# G474VET6_V3_1.net
KiCad netlist of a schematic drawn in EasyEDA Pro
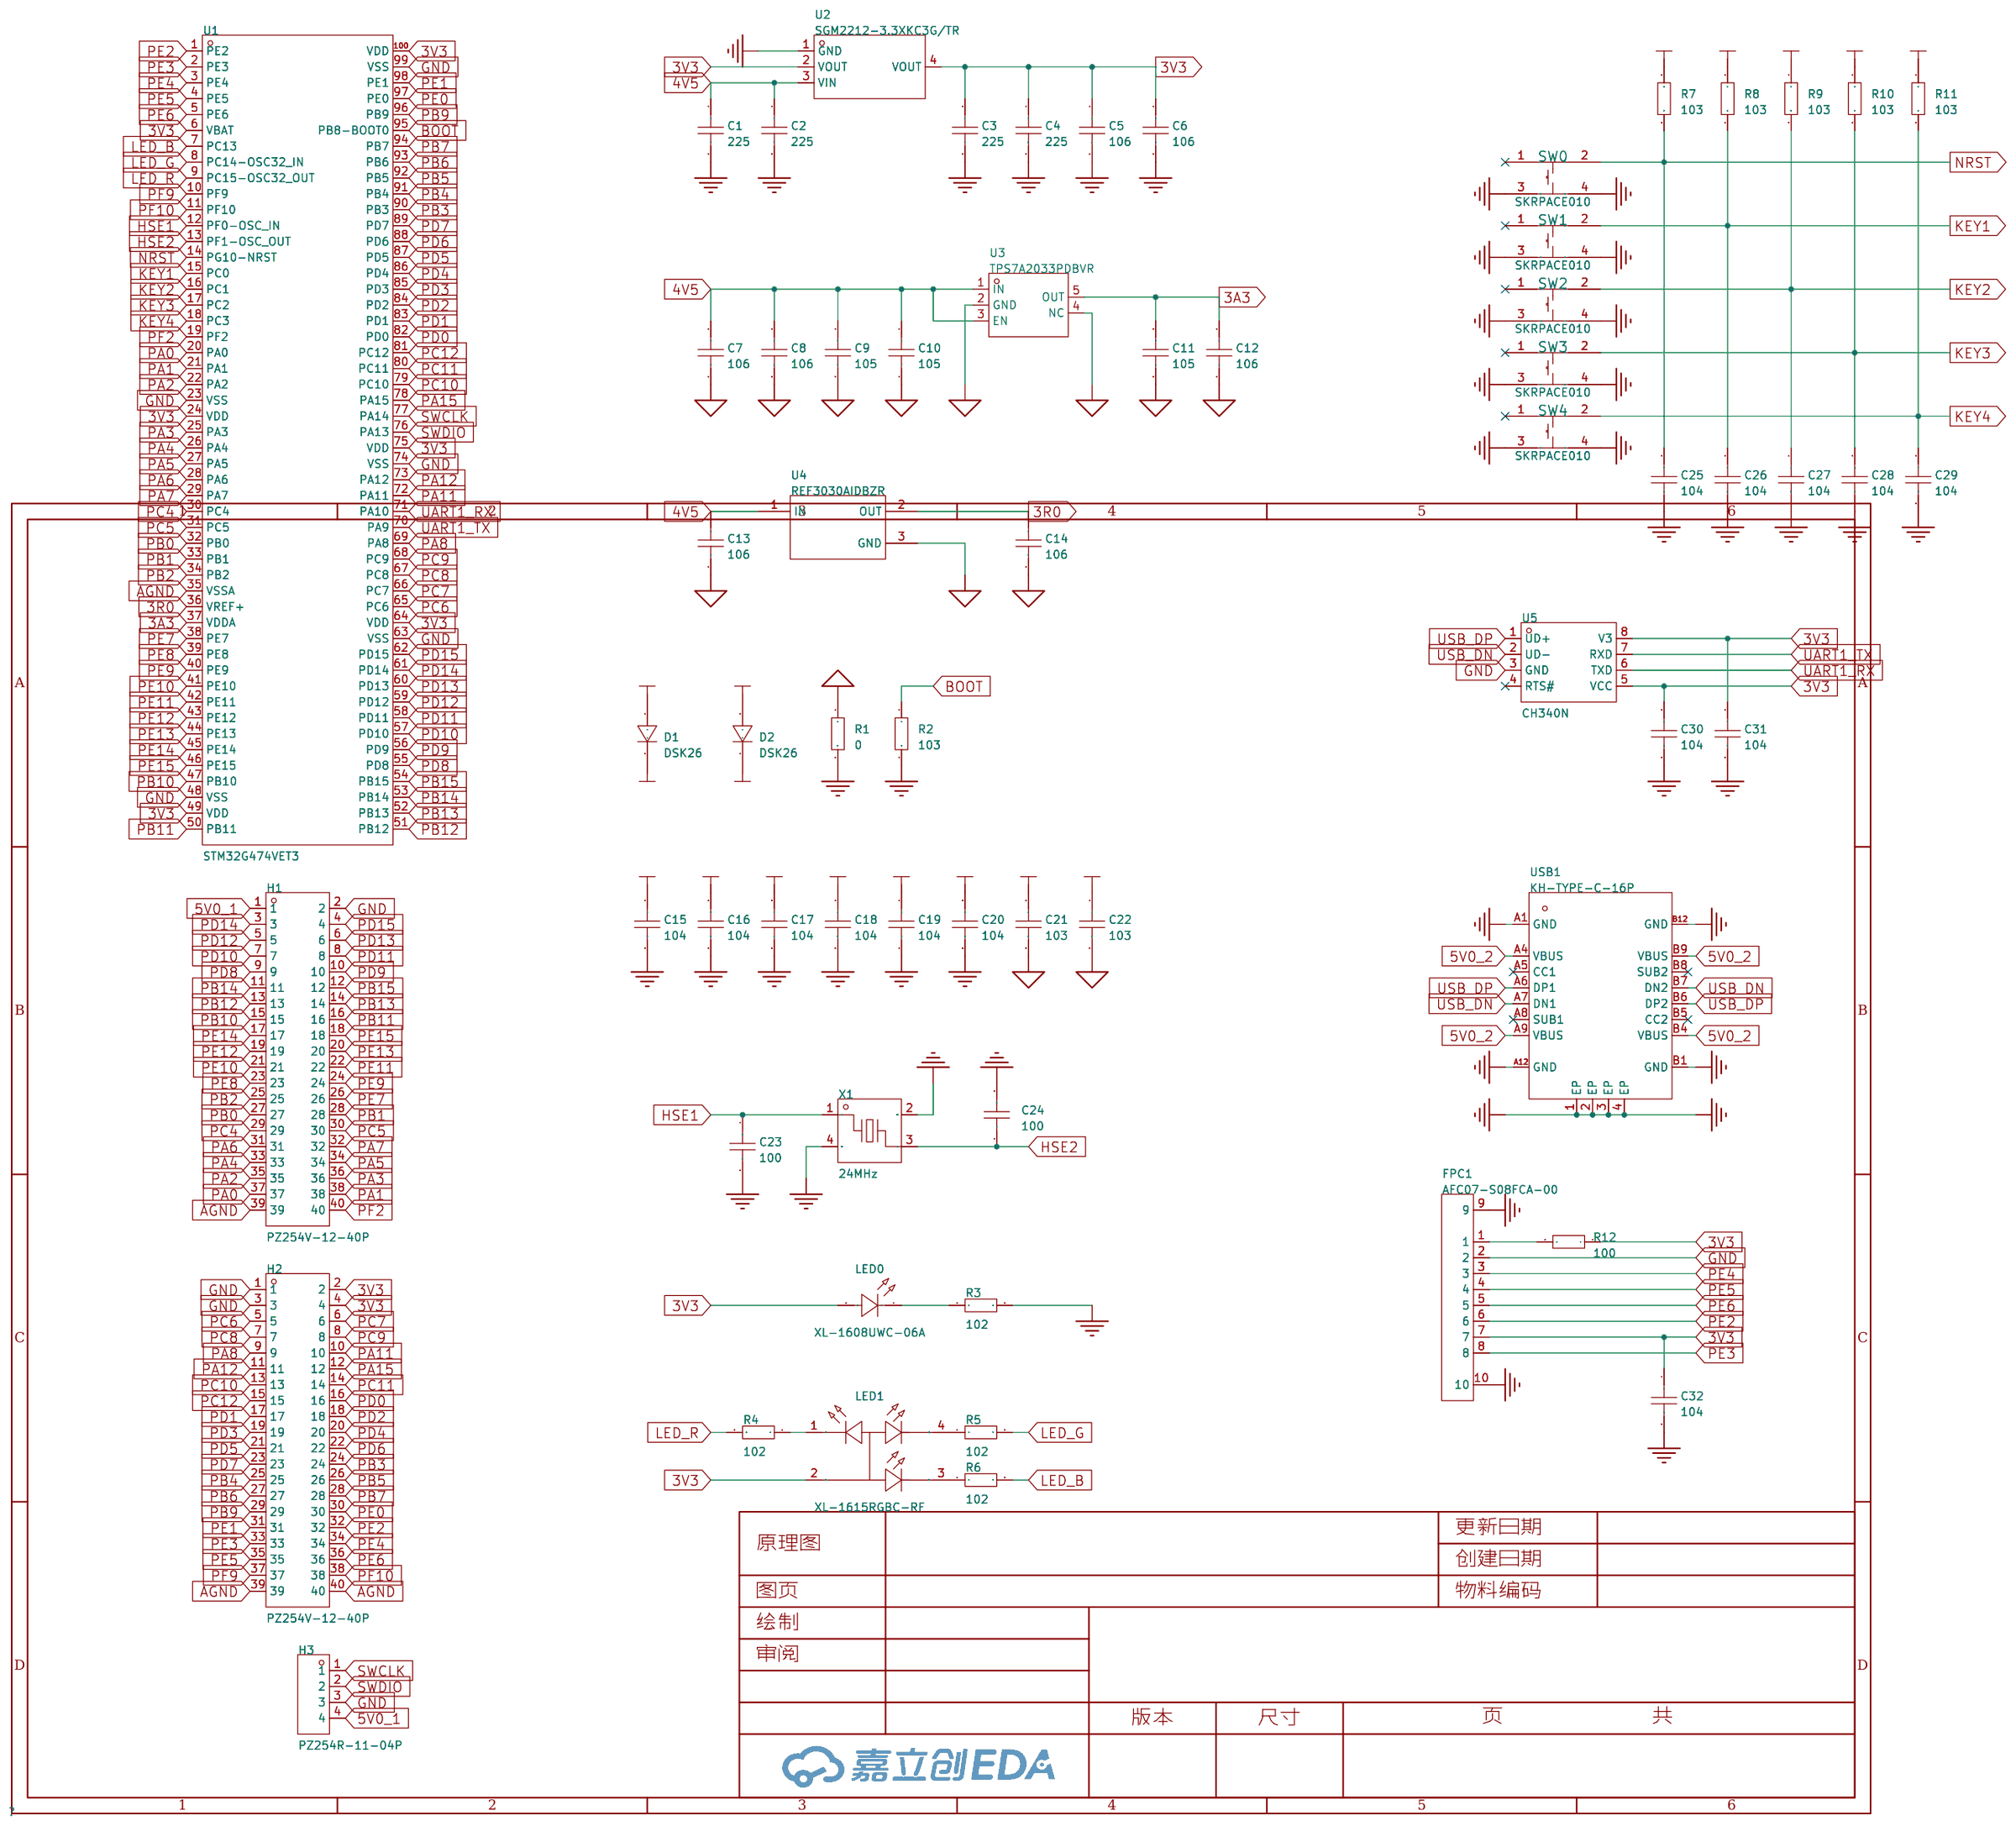
[diagram p0: schematic sheet]

(export (version "E")
  (design (tool "Eeschema 10.0.6"))
  (components
    (comp (ref "C1")
      (value "225")
      (footprint "easyedapro:C0603")
      (libsource (lib "easyedapro") (part "CapAcitance"))
    )
    (comp (ref "C2")
      (value "225")
      (footprint "easyedapro:C0603")
      (libsource (lib "easyedapro") (part "CapAcitance"))
    )
    (comp (ref "C3")
      (value "225")
      (footprint "easyedapro:C0603")
      (libsource (lib "easyedapro") (part "CapAcitance"))
    )
    (comp (ref "C4")
      (value "225")
      (footprint "easyedapro:C0603")
      (libsource (lib "easyedapro") (part "CapAcitance"))
    )
    (comp (ref "C5")
      (value "106")
      (footprint "easyedapro:C0603")
      (libsource (lib "easyedapro") (part "CapAcitance"))
    )
    (comp (ref "C6")
      (value "106")
      (footprint "easyedapro:C0603")
      (libsource (lib "easyedapro") (part "CapAcitance"))
    )
    (comp (ref "C7")
      (value "106")
      (footprint "easyedapro:C0603")
      (libsource (lib "easyedapro") (part "CapAcitance"))
    )
    (comp (ref "C8")
      (value "106")
      (footprint "easyedapro:C0603")
      (libsource (lib "easyedapro") (part "CapAcitance"))
    )
    (comp (ref "C9")
      (value "105")
      (footprint "easyedapro:C0603")
      (libsource (lib "easyedapro") (part "CapAcitance"))
    )
    (comp (ref "C10")
      (value "105")
      (footprint "easyedapro:C0603")
      (libsource (lib "easyedapro") (part "CapAcitance"))
    )
    (comp (ref "C11")
      (value "105")
      (footprint "easyedapro:C0603")
      (libsource (lib "easyedapro") (part "CapAcitance"))
    )
    (comp (ref "C12")
      (value "106")
      (footprint "easyedapro:C0603")
      (libsource (lib "easyedapro") (part "CapAcitance"))
    )
    (comp (ref "C13")
      (value "106")
      (footprint "easyedapro:C0603")
      (libsource (lib "easyedapro") (part "CapAcitance"))
    )
    (comp (ref "C14")
      (value "106")
      (footprint "easyedapro:C0603")
      (libsource (lib "easyedapro") (part "CapAcitance"))
    )
    (comp (ref "C15")
      (value "104")
      (footprint "easyedapro:C0603")
      (libsource (lib "easyedapro") (part "CapAcitance"))
    )
    (comp (ref "C16")
      (value "104")
      (footprint "easyedapro:C0603")
      (libsource (lib "easyedapro") (part "CapAcitance"))
    )
    (comp (ref "C17")
      (value "104")
      (footprint "easyedapro:C0603")
      (libsource (lib "easyedapro") (part "CapAcitance"))
    )
    (comp (ref "C18")
      (value "104")
      (footprint "easyedapro:C0603")
      (libsource (lib "easyedapro") (part "CapAcitance"))
    )
    (comp (ref "C19")
      (value "104")
      (footprint "easyedapro:C0603")
      (libsource (lib "easyedapro") (part "CapAcitance"))
    )
    (comp (ref "C20")
      (value "104")
      (footprint "easyedapro:C0603")
      (libsource (lib "easyedapro") (part "CapAcitance"))
    )
    (comp (ref "C21")
      (value "103")
      (footprint "easyedapro:C0603")
      (libsource (lib "easyedapro") (part "CapAcitance"))
    )
    (comp (ref "C22")
      (value "103")
      (footprint "easyedapro:C0603")
      (libsource (lib "easyedapro") (part "CapAcitance"))
    )
    (comp (ref "C23")
      (value "100")
      (footprint "easyedapro:C0603")
      (libsource (lib "easyedapro") (part "CapAcitance"))
    )
    (comp (ref "C24")
      (value "100")
      (footprint "easyedapro:C0603")
      (libsource (lib "easyedapro") (part "CapAcitance"))
    )
    (comp (ref "C25")
      (value "104")
      (footprint "easyedapro:C0603")
      (libsource (lib "easyedapro") (part "CapAcitance"))
    )
    (comp (ref "C26")
      (value "104")
      (footprint "easyedapro:C0603")
      (libsource (lib "easyedapro") (part "CapAcitance"))
    )
    (comp (ref "C27")
      (value "104")
      (footprint "easyedapro:C0603")
      (libsource (lib "easyedapro") (part "CapAcitance"))
    )
    (comp (ref "C28")
      (value "104")
      (footprint "easyedapro:C0603")
      (libsource (lib "easyedapro") (part "CapAcitance"))
    )
    (comp (ref "C29")
      (value "104")
      (footprint "easyedapro:C0603")
      (libsource (lib "easyedapro") (part "CapAcitance"))
    )
    (comp (ref "C30")
      (value "104")
      (footprint "easyedapro:C0603")
      (libsource (lib "easyedapro") (part "CapAcitance"))
    )
    (comp (ref "C31")
      (value "104")
      (footprint "easyedapro:C0603")
      (libsource (lib "easyedapro") (part "CapAcitance"))
    )
    (comp (ref "C32")
      (value "104")
      (footprint "easyedapro:C0603")
      (libsource (lib "easyedapro") (part "CapAcitance"))
    )
    (comp (ref "D1")
      (value "DSK26")
      (footprint "easyedapro:SOD-123_L2.8-W1.8-LS3.7-RD")
      (description "二极管配置:独立式;正向压降(Vf):700mV@2A;直流反向耐压(Vr):60V;整流电流:2A;")
      (fields (field (name "Manufacturer") "MDD(辰达半导体)"))
      (libsource (lib "easyedapro") (part "DSK26"))
    )
    (comp (ref "D2")
      (value "DSK26")
      (footprint "easyedapro:SOD-123_L2.8-W1.8-LS3.7-RD")
      (description "二极管配置:独立式;正向压降(Vf):700mV@2A;直流反向耐压(Vr):60V;整流电流:2A;")
      (fields (field (name "Manufacturer") "MDD(辰达半导体)"))
      (libsource (lib "easyedapro") (part "DSK26"))
    )
    (comp (ref "FPC1")
      (value "AFC07-S08FCA-00")
      (footprint "easyedapro:FPC-SMD_AFC07-S08FCA-00")
      (description "锁定特性:抽屉式;触点类型:下接;触点数量:8P;间距:0.5mm;安装类型:卧贴;")
      (fields (field (name "Manufacturer") "JS(钜硕电子)"))
      (libsource (lib "easyedapro") (part "AFC07-S08FCA-00"))
    )
    (comp (ref "H1")
      (value "PZ254V-12-40P")
      (footprint "easyedapro:HDR-TH_40P-P2.54-V-M-R2-C20-S2.54_2-146257-0")
      (description "排针2.54mm间距 双排 2x20P 直插 方针")
      (fields (field (name "Manufacturer") "XFCN(兴飞)"))
      (libsource (lib "easyedapro") (part "PZ254V-12-40P"))
    )
    (comp (ref "H2")
      (value "PZ254V-12-40P")
      (footprint "easyedapro:HDR-TH_40P-P2.54-V-M-R2-C20-S2.54_2-146257-0")
      (description "排针2.54mm间距 双排 2x20P 直插 方针")
      (fields (field (name "Manufacturer") "XFCN(兴飞)"))
      (libsource (lib "easyedapro") (part "PZ254V-12-40P"))
    )
    (comp (ref "H3")
      (value "PZ254R-11-04P")
      (footprint "easyedapro:HDR-TH_4P-P2.54-H-M-W10.4")
      (fields (field (name "Manufacturer") "XFCN(兴飞)"))
      (libsource (lib "easyedapro") (part "PZ254R-11-04P"))
    )
    (comp (ref "LED0")
      (value "XL-1608UWC-06A")
      (footprint "easyedapro:LED0603-RD_1")
      (fields (field (name "Manufacturer") "XINGLIGHT(成兴光)"))
      (libsource (lib "easyedapro") (part "XL-1608UWC-06A"))
    )
    (comp (ref "LED1")
      (value "XL-1615RGBC-RF")
      (footprint "easyedapro:LED-ARRAY-SMD_4P-L1.6-W1.5-BR_XL-1615RGBC-RF")
      (fields (field (name "Manufacturer") "XINGLIGHT(成兴光)"))
      (libsource (lib "easyedapro") (part "XL-1615RGBC-RF"))
    )
    (comp (ref "R1") (value "0") (footprint "easyedapro:R0603") (libsource (lib "easyedapro") (part "电阻")))
    (comp (ref "R2") (value "103") (footprint "easyedapro:R0603") (libsource (lib "easyedapro") (part "电阻")))
    (comp (ref "R3") (value "102") (footprint "easyedapro:R0603") (libsource (lib "easyedapro") (part "电阻")))
    (comp (ref "R4") (value "102") (footprint "easyedapro:R0603") (libsource (lib "easyedapro") (part "电阻")))
    (comp (ref "R5") (value "102") (footprint "easyedapro:R0603") (libsource (lib "easyedapro") (part "电阻")))
    (comp (ref "R6") (value "102") (footprint "easyedapro:R0603") (libsource (lib "easyedapro") (part "电阻")))
    (comp (ref "R7") (value "103") (footprint "easyedapro:R0603") (libsource (lib "easyedapro") (part "电阻")))
    (comp (ref "R8") (value "103") (footprint "easyedapro:R0603") (libsource (lib "easyedapro") (part "电阻")))
    (comp (ref "R9") (value "103") (footprint "easyedapro:R0603") (libsource (lib "easyedapro") (part "电阻")))
    (comp (ref "R10") (value "103") (footprint "easyedapro:R0603") (libsource (lib "easyedapro") (part "电阻")))
    (comp (ref "R11") (value "103") (footprint "easyedapro:R0603") (libsource (lib "easyedapro") (part "电阻")))
    (comp (ref "R12") (value "100") (footprint "easyedapro:R0603") (libsource (lib "easyedapro") (part "电阻")))
    (comp (ref "SW0")
      (value "SKRPACE010")
      (footprint "easyedapro:KEY-SMD_4P-L4.2-W3.2-P2.20-LS4.6")
      (description "电路结构:单刀单掷;按钮形状:椭圆形按钮;安装方式:立贴;开关长度:4.2mm;开关宽度:3.2mm;开关高度:2.5mm;触点电流:50mA;额定电压(DC):16V;带灯:-;机械寿命:-;")
      (fields (field (name "Manufacturer") "ALPSALPINE(阿尔卑斯阿尔派)"))
      (libsource (lib "easyedapro") (part "SKRPACE010"))
    )
    (comp (ref "SW1")
      (value "SKRPACE010")
      (footprint "easyedapro:KEY-SMD_4P-L4.2-W3.2-P2.20-LS4.6")
      (description "电路结构:单刀单掷;按钮形状:椭圆形按钮;安装方式:立贴;开关长度:4.2mm;开关宽度:3.2mm;开关高度:2.5mm;触点电流:50mA;额定电压(DC):16V;带灯:-;机械寿命:-;")
      (fields (field (name "Manufacturer") "ALPSALPINE(阿尔卑斯阿尔派)"))
      (libsource (lib "easyedapro") (part "SKRPACE010"))
    )
    (comp (ref "SW2")
      (value "SKRPACE010")
      (footprint "easyedapro:KEY-SMD_4P-L4.2-W3.2-P2.20-LS4.6")
      (description "电路结构:单刀单掷;按钮形状:椭圆形按钮;安装方式:立贴;开关长度:4.2mm;开关宽度:3.2mm;开关高度:2.5mm;触点电流:50mA;额定电压(DC):16V;带灯:-;机械寿命:-;")
      (fields (field (name "Manufacturer") "ALPSALPINE(阿尔卑斯阿尔派)"))
      (libsource (lib "easyedapro") (part "SKRPACE010"))
    )
    (comp (ref "SW3")
      (value "SKRPACE010")
      (footprint "easyedapro:KEY-SMD_4P-L4.2-W3.2-P2.20-LS4.6")
      (description "电路结构:单刀单掷;按钮形状:椭圆形按钮;安装方式:立贴;开关长度:4.2mm;开关宽度:3.2mm;开关高度:2.5mm;触点电流:50mA;额定电压(DC):16V;带灯:-;机械寿命:-;")
      (fields (field (name "Manufacturer") "ALPSALPINE(阿尔卑斯阿尔派)"))
      (libsource (lib "easyedapro") (part "SKRPACE010"))
    )
    (comp (ref "SW4")
      (value "SKRPACE010")
      (footprint "easyedapro:KEY-SMD_4P-L4.2-W3.2-P2.20-LS4.6")
      (description "电路结构:单刀单掷;按钮形状:椭圆形按钮;安装方式:立贴;开关长度:4.2mm;开关宽度:3.2mm;开关高度:2.5mm;触点电流:50mA;额定电压(DC):16V;带灯:-;机械寿命:-;")
      (fields (field (name "Manufacturer") "ALPSALPINE(阿尔卑斯阿尔派)"))
      (libsource (lib "easyedapro") (part "SKRPACE010"))
    )
    (comp (ref "U1")
      (value "STM32G474VET3")
      (footprint "easyedapro:LQFP-100_L14.0-W14.0-P0.50-LS16.0-BL")
      (description "CPU内核:-;程序存储容量:512KB;GPIO端口数量:86;工作电压范围:1.71V~3.6V;CPU最大主频:170MHz;")
      (fields (field (name "Manufacturer") "ST(意法半导体)"))
      (libsource (lib "easyedapro") (part "STM32G474VET3"))
    )
    (comp (ref "U2")
      (value "SGM2212-3.3XKC3G/TR")
      (footprint "easyedapro:SOT-223-3_L6.5-W3.4-P2.30-LS7.0-BR")
      (fields (field (name "Manufacturer") "SGMICRO(圣邦微)"))
      (libsource (lib "easyedapro") (part "SGM2212-3.3XKC3G/TR_C3294699"))
    )
    (comp (ref "U3")
      (value "TPS7A2033PDBVR")
      (footprint "easyedapro:SOT-23-5_L2.9-W1.6-P0.95-LS2.8-BR")
      (description "输出类型:固定;最大输入电压:6V;输出电压:3.3V;输出电流:300mA;输出极性:正极;")
      (fields (field (name "Manufacturer") "TI(德州仪器)"))
      (libsource (lib "easyedapro") (part "TPS7A2033PDBVR"))
    )
    (comp (ref "U4")
      (value "REF3030AIDBZR")
      (footprint "easyedapro:SOT-23-3_L2.9-W1.6-P1.90-LS2.8-BR")
      (description "输出类型:固定;输入电压:3.05V~5.5V;输出电压:3V;输出电流:25mA;精度:±0.2%;")
      (fields (field (name "Manufacturer") "TI(德州仪器)"))
      (libsource (lib "easyedapro") (part "REF3030AIDBZR"))
    )
    (comp (ref "U5")
      (value "CH340N")
      (footprint "easyedapro:SOP-8_L4.9-W3.9-P1.27-LS6.0-BL")
      (fields (field (name "Manufacturer") "WCH(南京沁恒)"))
      (libsource (lib "easyedapro") (part "CH340N_C2977777"))
    )
    (comp (ref "USB1")
      (value "KH-TYPE-C-16P")
      (footprint "easyedapro:USB-C-SMD_KH-TYPE-C-16P")
      (description "连接器类型:Type-C;标准:-;公母:母;端口数量:1;触点数量:16P;安装方式:卧贴;额定电流 - 电源:3A;工作温度范围:-40°C~+85°C;")
      (fields (field (name "Manufacturer") "kinghelm(金航标)"))
      (libsource (lib "easyedapro") (part "KH-TYPE-C-16P"))
    )
    (comp (ref "X1")
      (value "24MHz")
      (footprint "easyedapro:CRYSTAL-SMD_4P-L2.0-W1.6-BL")
      (description "晶振类型:贴片晶振;频率:24MHz;常温频差:±10ppm;外接负载电容:10pF;频率稳定度(全温):±20ppm;")
      (fields
        (field (name "Manufacturer Part") "XL7EL89CMI-111YLC-24M")
        (field (name "Manufacturer") "YXC(扬兴晶振)")
      )
      (libsource (lib "easyedapro") (part "XL7EL89CMI-111YLC-24M"))
    )
  )
  (nets
    (net (code "1") (name "3A3") (class "Default")
      (node (ref "C11") (pin "1") (pinfunction "1_1") (pintype "input"))
      (node (ref "C12") (pin "1") (pinfunction "1_1") (pintype "input"))
      (node (ref "C21") (pin "1") (pinfunction "1_1") (pintype "input"))
      (node (ref "U1") (pin "37") (pinfunction "VDDA_37") (pintype "unspecified"))
      (node (ref "U3") (pin "5") (pinfunction "OUT_5") (pintype "unspecified"))
    )
    (net (code "2") (name "3R0") (class "Default")
      (node (ref "C14") (pin "1") (pinfunction "1_1") (pintype "input"))
      (node (ref "C22") (pin "1") (pinfunction "1_1") (pintype "input"))
      (node (ref "U1") (pin "36") (pinfunction "VREF+_36") (pintype "unspecified"))
      (node (ref "U4") (pin "2") (pinfunction "OUT_2") (pintype "unspecified"))
    )
    (net (code "3") (name "3V3") (class "Default")
      (node (ref "C15") (pin "1") (pinfunction "1_1") (pintype "input"))
      (node (ref "C16") (pin "1") (pinfunction "1_1") (pintype "input"))
      (node (ref "C17") (pin "1") (pinfunction "1_1") (pintype "input"))
      (node (ref "C18") (pin "1") (pinfunction "1_1") (pintype "input"))
      (node (ref "C19") (pin "1") (pinfunction "1_1") (pintype "input"))
      (node (ref "C20") (pin "1") (pinfunction "1_1") (pintype "input"))
      (node (ref "C3") (pin "1") (pinfunction "1_1") (pintype "input"))
      (node (ref "C30") (pin "1") (pinfunction "1_1") (pintype "input"))
      (node (ref "C31") (pin "1") (pinfunction "1_1") (pintype "input"))
      (node (ref "C32") (pin "1") (pinfunction "1_1") (pintype "input"))
      (node (ref "C4") (pin "1") (pinfunction "1_1") (pintype "input"))
      (node (ref "C5") (pin "1") (pinfunction "1_1") (pintype "input"))
      (node (ref "C6") (pin "1") (pinfunction "1_1") (pintype "input"))
      (node (ref "FPC1") (pin "7") (pinfunction "7_7") (pintype "unspecified"))
      (node (ref "H2") (pin "2") (pinfunction "2_2") (pintype "unspecified"))
      (node (ref "H2") (pin "4") (pinfunction "4_4") (pintype "unspecified"))
      (node (ref "LED0") (pin "2") (pinfunction "A_2") (pintype "unspecified"))
      (node (ref "LED1") (pin "2") (pinfunction "COM+_2") (pintype "unspecified"))
      (node (ref "R10") (pin "1") (pinfunction "1_1") (pintype "input"))
      (node (ref "R11") (pin "1") (pinfunction "1_1") (pintype "input"))
      (node (ref "R12") (pin "1") (pinfunction "1_1") (pintype "input"))
      (node (ref "R7") (pin "1") (pinfunction "1_1") (pintype "input"))
      (node (ref "R8") (pin "1") (pinfunction "1_1") (pintype "input"))
      (node (ref "R9") (pin "1") (pinfunction "1_1") (pintype "input"))
      (node (ref "U1") (pin "100") (pinfunction "VDD_100") (pintype "unspecified"))
      (node (ref "U1") (pin "24") (pinfunction "VDD_24") (pintype "unspecified"))
      (node (ref "U1") (pin "49") (pinfunction "VDD_49") (pintype "unspecified"))
      (node (ref "U1") (pin "6") (pinfunction "VBAT_6") (pintype "unspecified"))
      (node (ref "U1") (pin "64") (pinfunction "VDD_64") (pintype "unspecified"))
      (node (ref "U1") (pin "75") (pinfunction "VDD_75") (pintype "unspecified"))
      (node (ref "U2") (pin "2") (pinfunction "VOUT_2") (pintype "unspecified"))
      (node (ref "U2") (pin "4") (pinfunction "VOUT_4") (pintype "unspecified"))
      (node (ref "U5") (pin "5") (pinfunction "VCC_5") (pintype "unspecified"))
      (node (ref "U5") (pin "8") (pinfunction "V3_8") (pintype "unspecified"))
    )
    (net (code "4") (name "4V5") (class "Default")
      (node (ref "C1") (pin "1") (pinfunction "1_1") (pintype "input"))
      (node (ref "C10") (pin "1") (pinfunction "1_1") (pintype "input"))
      (node (ref "C13") (pin "1") (pinfunction "1_1") (pintype "input"))
      (node (ref "C2") (pin "1") (pinfunction "1_1") (pintype "input"))
      (node (ref "C7") (pin "1") (pinfunction "1_1") (pintype "input"))
      (node (ref "C8") (pin "1") (pinfunction "1_1") (pintype "input"))
      (node (ref "C9") (pin "1") (pinfunction "1_1") (pintype "input"))
      (node (ref "D1") (pin "1") (pinfunction "K_1") (pintype "unspecified"))
      (node (ref "D2") (pin "1") (pinfunction "K_1") (pintype "unspecified"))
      (node (ref "U2") (pin "3") (pinfunction "VIN_3") (pintype "unspecified"))
      (node (ref "U3") (pin "1") (pinfunction "IN_1") (pintype "unspecified"))
      (node (ref "U3") (pin "3") (pinfunction "EN_3") (pintype "unspecified"))
      (node (ref "U4") (pin "1") (pinfunction "IN_1") (pintype "unspecified"))
    )
    (net (code "5") (name "5V0_1") (class "Default")
      (node (ref "D1") (pin "2") (pinfunction "A_2") (pintype "unspecified"))
      (node (ref "H1") (pin "1") (pinfunction "1_1") (pintype "unspecified"))
      (node (ref "H3") (pin "4") (pinfunction "4_4") (pintype "unspecified"))
    )
    (net (code "6") (name "5V0_2") (class "Default")
      (node (ref "D2") (pin "2") (pinfunction "A_2") (pintype "unspecified"))
      (node (ref "USB1") (pin "A4") (pinfunction "VBUS_A4") (pintype "unspecified"))
      (node (ref "USB1") (pin "A9") (pinfunction "VBUS_A9") (pintype "unspecified"))
      (node (ref "USB1") (pin "B4") (pinfunction "VBUS_B4") (pintype "unspecified"))
      (node (ref "USB1") (pin "B9") (pinfunction "VBUS_B9") (pintype "unspecified"))
    )
    (net (code "7") (name "AGND") (class "Default")
      (node (ref "C10") (pin "2") (pinfunction "2_2") (pintype "input"))
      (node (ref "C11") (pin "2") (pinfunction "2_2") (pintype "input"))
      (node (ref "C12") (pin "2") (pinfunction "2_2") (pintype "input"))
      (node (ref "C13") (pin "2") (pinfunction "2_2") (pintype "input"))
      (node (ref "C14") (pin "2") (pinfunction "2_2") (pintype "input"))
      (node (ref "C21") (pin "2") (pinfunction "2_2") (pintype "input"))
      (node (ref "C22") (pin "2") (pinfunction "2_2") (pintype "input"))
      (node (ref "C7") (pin "2") (pinfunction "2_2") (pintype "input"))
      (node (ref "C8") (pin "2") (pinfunction "2_2") (pintype "input"))
      (node (ref "C9") (pin "2") (pinfunction "2_2") (pintype "input"))
      (node (ref "H1") (pin "39") (pinfunction "39_39") (pintype "unspecified"))
      (node (ref "H2") (pin "39") (pinfunction "39_39") (pintype "unspecified"))
      (node (ref "H2") (pin "40") (pinfunction "40_40") (pintype "unspecified"))
      (node (ref "R1") (pin "1") (pinfunction "1_1") (pintype "input"))
      (node (ref "U1") (pin "35") (pinfunction "VSSA_35") (pintype "unspecified"))
      (node (ref "U3") (pin "2") (pinfunction "GND_2") (pintype "unspecified"))
      (node (ref "U3") (pin "4") (pinfunction "NC_4") (pintype "unspecified"))
      (node (ref "U4") (pin "3") (pinfunction "GND_3") (pintype "unspecified"))
    )
    (net (code "8") (name "BOOT") (class "Default")
      (node (ref "R2") (pin "1") (pinfunction "1_1") (pintype "input"))
      (node (ref "U1") (pin "95") (pinfunction "PB8-BOOT0_95") (pintype "unspecified"))
    )
    (net (code "9") (name "GND") (class "Default")
      (node (ref "C1") (pin "2") (pinfunction "2_2") (pintype "input"))
      (node (ref "C15") (pin "2") (pinfunction "2_2") (pintype "input"))
      (node (ref "C16") (pin "2") (pinfunction "2_2") (pintype "input"))
      (node (ref "C17") (pin "2") (pinfunction "2_2") (pintype "input"))
      (node (ref "C18") (pin "2") (pinfunction "2_2") (pintype "input"))
      (node (ref "C19") (pin "2") (pinfunction "2_2") (pintype "input"))
      (node (ref "C2") (pin "2") (pinfunction "2_2") (pintype "input"))
      (node (ref "C20") (pin "2") (pinfunction "2_2") (pintype "input"))
      (node (ref "C23") (pin "2") (pinfunction "2_2") (pintype "input"))
      (node (ref "C24") (pin "2") (pinfunction "2_2") (pintype "input"))
      (node (ref "C25") (pin "2") (pinfunction "2_2") (pintype "input"))
      (node (ref "C26") (pin "2") (pinfunction "2_2") (pintype "input"))
      (node (ref "C27") (pin "2") (pinfunction "2_2") (pintype "input"))
      (node (ref "C28") (pin "2") (pinfunction "2_2") (pintype "input"))
      (node (ref "C29") (pin "2") (pinfunction "2_2") (pintype "input"))
      (node (ref "C3") (pin "2") (pinfunction "2_2") (pintype "input"))
      (node (ref "C30") (pin "2") (pinfunction "2_2") (pintype "input"))
      (node (ref "C31") (pin "2") (pinfunction "2_2") (pintype "input"))
      (node (ref "C32") (pin "2") (pinfunction "2_2") (pintype "input"))
      (node (ref "C4") (pin "2") (pinfunction "2_2") (pintype "input"))
      (node (ref "C5") (pin "2") (pinfunction "2_2") (pintype "input"))
      (node (ref "C6") (pin "2") (pinfunction "2_2") (pintype "input"))
      (node (ref "FPC1") (pin "10") (pinfunction "10_10") (pintype "unspecified"))
      (node (ref "FPC1") (pin "2") (pinfunction "2_2") (pintype "unspecified"))
      (node (ref "FPC1") (pin "9") (pinfunction "9_9") (pintype "unspecified"))
      (node (ref "H1") (pin "2") (pinfunction "2_2") (pintype "unspecified"))
      (node (ref "H2") (pin "1") (pinfunction "1_1") (pintype "unspecified"))
      (node (ref "H2") (pin "3") (pinfunction "3_3") (pintype "unspecified"))
      (node (ref "H3") (pin "3") (pinfunction "3_3") (pintype "unspecified"))
      (node (ref "R1") (pin "2") (pinfunction "2_2") (pintype "input"))
      (node (ref "R2") (pin "2") (pinfunction "2_2") (pintype "input"))
      (node (ref "R3") (pin "2") (pinfunction "2_2") (pintype "input"))
      (node (ref "SW0") (pin "3") (pinfunction "3_3") (pintype "input"))
      (node (ref "SW0") (pin "4") (pinfunction "4_4") (pintype "input"))
      (node (ref "SW1") (pin "3") (pinfunction "3_3") (pintype "input"))
      (node (ref "SW1") (pin "4") (pinfunction "4_4") (pintype "input"))
      (node (ref "SW2") (pin "3") (pinfunction "3_3") (pintype "input"))
      (node (ref "SW2") (pin "4") (pinfunction "4_4") (pintype "input"))
      (node (ref "SW3") (pin "3") (pinfunction "3_3") (pintype "input"))
      (node (ref "SW3") (pin "4") (pinfunction "4_4") (pintype "input"))
      (node (ref "SW4") (pin "3") (pinfunction "3_3") (pintype "input"))
      (node (ref "SW4") (pin "4") (pinfunction "4_4") (pintype "input"))
      (node (ref "U1") (pin "23") (pinfunction "VSS_23") (pintype "unspecified"))
      (node (ref "U1") (pin "48") (pinfunction "VSS_48") (pintype "unspecified"))
      (node (ref "U1") (pin "63") (pinfunction "VSS_63") (pintype "unspecified"))
      (node (ref "U1") (pin "74") (pinfunction "VSS_74") (pintype "unspecified"))
      (node (ref "U1") (pin "99") (pinfunction "VSS_99") (pintype "unspecified"))
      (node (ref "U2") (pin "1") (pinfunction "GND_1") (pintype "unspecified"))
      (node (ref "U5") (pin "3") (pinfunction "GND_3") (pintype "unspecified"))
      (node (ref "USB1") (pin "1") (pinfunction "EP_1") (pintype "unspecified"))
      (node (ref "USB1") (pin "2") (pinfunction "EP_2") (pintype "unspecified"))
      (node (ref "USB1") (pin "3") (pinfunction "EP_3") (pintype "unspecified"))
      (node (ref "USB1") (pin "4") (pinfunction "EP_4") (pintype "unspecified"))
      (node (ref "USB1") (pin "A1") (pinfunction "GND_A1") (pintype "unspecified"))
      (node (ref "USB1") (pin "A12") (pinfunction "GND_A12") (pintype "unspecified"))
      (node (ref "USB1") (pin "B1") (pinfunction "GND_B1") (pintype "unspecified"))
      (node (ref "USB1") (pin "B12") (pinfunction "GND_B12") (pintype "unspecified"))
      (node (ref "X1") (pin "2") (pinfunction "GND_2") (pintype "input"))
      (node (ref "X1") (pin "4") (pinfunction "GND_4") (pintype "input"))
    )
    (net (code "10") (name "HSE1") (class "Default")
      (node (ref "C23") (pin "1") (pinfunction "1_1") (pintype "input"))
      (node (ref "U1") (pin "12") (pinfunction "PF0-OSC_IN_12") (pintype "unspecified"))
      (node (ref "X1") (pin "1") (pinfunction "1_1") (pintype "input"))
    )
    (net (code "11") (name "HSE2") (class "Default")
      (node (ref "C24") (pin "1") (pinfunction "1_1") (pintype "input"))
      (node (ref "U1") (pin "13") (pinfunction "PF1-OSC_OUT_13") (pintype "unspecified"))
      (node (ref "X1") (pin "3") (pinfunction "3_3") (pintype "input"))
    )
    (net (code "12") (name "KEY1") (class "Default")
      (node (ref "C26") (pin "1") (pinfunction "1_1") (pintype "input"))
      (node (ref "R8") (pin "2") (pinfunction "2_2") (pintype "input"))
      (node (ref "SW1") (pin "2") (pinfunction "2_2") (pintype "input"))
      (node (ref "U1") (pin "15") (pinfunction "PC0_15") (pintype "unspecified"))
    )
    (net (code "13") (name "KEY2") (class "Default")
      (node (ref "C27") (pin "1") (pinfunction "1_1") (pintype "input"))
      (node (ref "R9") (pin "2") (pinfunction "2_2") (pintype "input"))
      (node (ref "SW2") (pin "2") (pinfunction "2_2") (pintype "input"))
      (node (ref "U1") (pin "16") (pinfunction "PC1_16") (pintype "unspecified"))
    )
    (net (code "14") (name "KEY3") (class "Default")
      (node (ref "C28") (pin "1") (pinfunction "1_1") (pintype "input"))
      (node (ref "R10") (pin "2") (pinfunction "2_2") (pintype "input"))
      (node (ref "SW3") (pin "2") (pinfunction "2_2") (pintype "input"))
      (node (ref "U1") (pin "17") (pinfunction "PC2_17") (pintype "unspecified"))
    )
    (net (code "15") (name "KEY4") (class "Default")
      (node (ref "C29") (pin "1") (pinfunction "1_1") (pintype "input"))
      (node (ref "R11") (pin "2") (pinfunction "2_2") (pintype "input"))
      (node (ref "SW4") (pin "2") (pinfunction "2_2") (pintype "input"))
      (node (ref "U1") (pin "18") (pinfunction "PC3_18") (pintype "unspecified"))
    )
    (net (code "16") (name "LED_B") (class "Default")
      (node (ref "R6") (pin "2") (pinfunction "2_2") (pintype "input"))
      (node (ref "U1") (pin "7") (pinfunction "PC13_7") (pintype "unspecified"))
    )
    (net (code "17") (name "LED_G") (class "Default")
      (node (ref "R5") (pin "2") (pinfunction "2_2") (pintype "input"))
      (node (ref "U1") (pin "8") (pinfunction "PC14-OSC32_IN_8") (pintype "unspecified"))
    )
    (net (code "18") (name "LED_R") (class "Default")
      (node (ref "R4") (pin "2") (pinfunction "2_2") (pintype "input"))
      (node (ref "U1") (pin "9") (pinfunction "PC15-OSC32_OUT_9") (pintype "unspecified"))
    )
    (net (code "19") (name "NRST") (class "Default")
      (node (ref "C25") (pin "1") (pinfunction "1_1") (pintype "input"))
      (node (ref "R7") (pin "2") (pinfunction "2_2") (pintype "input"))
      (node (ref "SW0") (pin "2") (pinfunction "2_2") (pintype "input"))
      (node (ref "U1") (pin "14") (pinfunction "PG10-NRST_14") (pintype "unspecified"))
    )
    (net (code "20") (name "Net-(FPC1-Pad1)") (class "Default")
      (node (ref "FPC1") (pin "1") (pinfunction "1_1") (pintype "unspecified"))
      (node (ref "R12") (pin "2") (pinfunction "2_2") (pintype "input"))
    )
    (net (code "21") (name "Net-(LED0-K)") (class "Default")
      (node (ref "LED0") (pin "1") (pinfunction "K_1") (pintype "unspecified"))
      (node (ref "R3") (pin "1") (pinfunction "1_1") (pintype "input"))
    )
    (net (code "22") (name "Net-(LED1-B-)") (class "Default")
      (node (ref "LED1") (pin "3") (pinfunction "B-_3") (pintype "unspecified"))
      (node (ref "R6") (pin "1") (pinfunction "1_1") (pintype "input"))
    )
    (net (code "23") (name "Net-(LED1-G-)") (class "Default")
      (node (ref "LED1") (pin "4") (pinfunction "G-_4") (pintype "unspecified"))
      (node (ref "R5") (pin "1") (pinfunction "1_1") (pintype "input"))
    )
    (net (code "24") (name "Net-(LED1-R-)") (class "Default")
      (node (ref "LED1") (pin "1") (pinfunction "R-_1") (pintype "unspecified"))
      (node (ref "R4") (pin "1") (pinfunction "1_1") (pintype "input"))
    )
    (net (code "25") (name "PA0") (class "Default")
      (node (ref "H1") (pin "37") (pinfunction "37_37") (pintype "unspecified"))
      (node (ref "U1") (pin "20") (pinfunction "PA0_20") (pintype "unspecified"))
    )
    (net (code "26") (name "PA1") (class "Default")
      (node (ref "H1") (pin "38") (pinfunction "38_38") (pintype "unspecified"))
      (node (ref "U1") (pin "21") (pinfunction "PA1_21") (pintype "unspecified"))
    )
    (net (code "27") (name "PA2") (class "Default")
      (node (ref "H1") (pin "35") (pinfunction "35_35") (pintype "unspecified"))
      (node (ref "U1") (pin "22") (pinfunction "PA2_22") (pintype "unspecified"))
    )
    (net (code "28") (name "PA3") (class "Default")
      (node (ref "H1") (pin "36") (pinfunction "36_36") (pintype "unspecified"))
      (node (ref "U1") (pin "25") (pinfunction "PA3_25") (pintype "unspecified"))
    )
    (net (code "29") (name "PA4") (class "Default")
      (node (ref "H1") (pin "33") (pinfunction "33_33") (pintype "unspecified"))
      (node (ref "U1") (pin "26") (pinfunction "PA4_26") (pintype "unspecified"))
    )
    (net (code "30") (name "PA5") (class "Default")
      (node (ref "H1") (pin "34") (pinfunction "34_34") (pintype "unspecified"))
      (node (ref "U1") (pin "27") (pinfunction "PA5_27") (pintype "unspecified"))
    )
    (net (code "31") (name "PA6") (class "Default")
      (node (ref "H1") (pin "31") (pinfunction "31_31") (pintype "unspecified"))
      (node (ref "U1") (pin "28") (pinfunction "PA6_28") (pintype "unspecified"))
    )
    (net (code "32") (name "PA7") (class "Default")
      (node (ref "H1") (pin "32") (pinfunction "32_32") (pintype "unspecified"))
      (node (ref "U1") (pin "29") (pinfunction "PA7_29") (pintype "unspecified"))
    )
    (net (code "33") (name "PA8") (class "Default")
      (node (ref "H2") (pin "9") (pinfunction "9_9") (pintype "unspecified"))
      (node (ref "U1") (pin "69") (pinfunction "PA8_69") (pintype "unspecified"))
    )
    (net (code "34") (name "PA11") (class "Default")
      (node (ref "H2") (pin "10") (pinfunction "10_10") (pintype "unspecified"))
      (node (ref "U1") (pin "72") (pinfunction "PA11_72") (pintype "unspecified"))
    )
    (net (code "35") (name "PA12") (class "Default")
      (node (ref "H2") (pin "11") (pinfunction "11_11") (pintype "unspecified"))
      (node (ref "U1") (pin "73") (pinfunction "PA12_73") (pintype "unspecified"))
    )
    (net (code "36") (name "PA15") (class "Default")
      (node (ref "H2") (pin "12") (pinfunction "12_12") (pintype "unspecified"))
      (node (ref "U1") (pin "78") (pinfunction "PA15_78") (pintype "unspecified"))
    )
    (net (code "37") (name "PB0") (class "Default")
      (node (ref "H1") (pin "27") (pinfunction "27_27") (pintype "unspecified"))
      (node (ref "U1") (pin "32") (pinfunction "PB0_32") (pintype "unspecified"))
    )
    (net (code "38") (name "PB1") (class "Default")
      (node (ref "H1") (pin "28") (pinfunction "28_28") (pintype "unspecified"))
      (node (ref "U1") (pin "33") (pinfunction "PB1_33") (pintype "unspecified"))
    )
    (net (code "39") (name "PB2") (class "Default")
      (node (ref "H1") (pin "25") (pinfunction "25_25") (pintype "unspecified"))
      (node (ref "U1") (pin "34") (pinfunction "PB2_34") (pintype "unspecified"))
    )
    (net (code "40") (name "PB3") (class "Default")
      (node (ref "H2") (pin "24") (pinfunction "24_24") (pintype "unspecified"))
      (node (ref "U1") (pin "90") (pinfunction "PB3_90") (pintype "unspecified"))
    )
    (net (code "41") (name "PB4") (class "Default")
      (node (ref "H2") (pin "25") (pinfunction "25_25") (pintype "unspecified"))
      (node (ref "U1") (pin "91") (pinfunction "PB4_91") (pintype "unspecified"))
    )
    (net (code "42") (name "PB5") (class "Default")
      (node (ref "H2") (pin "26") (pinfunction "26_26") (pintype "unspecified"))
      (node (ref "U1") (pin "92") (pinfunction "PB5_92") (pintype "unspecified"))
    )
    (net (code "43") (name "PB6") (class "Default")
      (node (ref "H2") (pin "27") (pinfunction "27_27") (pintype "unspecified"))
      (node (ref "U1") (pin "93") (pinfunction "PB6_93") (pintype "unspecified"))
    )
    (net (code "44") (name "PB7") (class "Default")
      (node (ref "H2") (pin "28") (pinfunction "28_28") (pintype "unspecified"))
      (node (ref "U1") (pin "94") (pinfunction "PB7_94") (pintype "unspecified"))
    )
    (net (code "45") (name "PB9") (class "Default")
      (node (ref "H2") (pin "29") (pinfunction "29_29") (pintype "unspecified"))
      (node (ref "U1") (pin "96") (pinfunction "PB9_96") (pintype "unspecified"))
    )
    (net (code "46") (name "PB10") (class "Default")
      (node (ref "H1") (pin "15") (pinfunction "15_15") (pintype "unspecified"))
      (node (ref "U1") (pin "47") (pinfunction "PB10_47") (pintype "unspecified"))
    )
    (net (code "47") (name "PB11") (class "Default")
      (node (ref "H1") (pin "16") (pinfunction "16_16") (pintype "unspecified"))
      (node (ref "U1") (pin "50") (pinfunction "PB11_50") (pintype "unspecified"))
    )
    (net (code "48") (name "PB12") (class "Default")
      (node (ref "H1") (pin "13") (pinfunction "13_13") (pintype "unspecified"))
      (node (ref "U1") (pin "51") (pinfunction "PB12_51") (pintype "unspecified"))
    )
    (net (code "49") (name "PB13") (class "Default")
      (node (ref "H1") (pin "14") (pinfunction "14_14") (pintype "unspecified"))
      (node (ref "U1") (pin "52") (pinfunction "PB13_52") (pintype "unspecified"))
    )
    (net (code "50") (name "PB14") (class "Default")
      (node (ref "H1") (pin "11") (pinfunction "11_11") (pintype "unspecified"))
      (node (ref "U1") (pin "53") (pinfunction "PB14_53") (pintype "unspecified"))
    )
    (net (code "51") (name "PB15") (class "Default")
      (node (ref "H1") (pin "12") (pinfunction "12_12") (pintype "unspecified"))
      (node (ref "U1") (pin "54") (pinfunction "PB15_54") (pintype "unspecified"))
    )
    (net (code "52") (name "PC4") (class "Default")
      (node (ref "H1") (pin "29") (pinfunction "29_29") (pintype "unspecified"))
      (node (ref "U1") (pin "30") (pinfunction "PC4_30") (pintype "unspecified"))
    )
    (net (code "53") (name "PC5") (class "Default")
      (node (ref "H1") (pin "30") (pinfunction "30_30") (pintype "unspecified"))
      (node (ref "U1") (pin "31") (pinfunction "PC5_31") (pintype "unspecified"))
    )
    (net (code "54") (name "PC6") (class "Default")
      (node (ref "H2") (pin "5") (pinfunction "5_5") (pintype "unspecified"))
      (node (ref "U1") (pin "65") (pinfunction "PC6_65") (pintype "unspecified"))
    )
    (net (code "55") (name "PC7") (class "Default")
      (node (ref "H2") (pin "6") (pinfunction "6_6") (pintype "unspecified"))
      (node (ref "U1") (pin "66") (pinfunction "PC7_66") (pintype "unspecified"))
    )
    (net (code "56") (name "PC8") (class "Default")
      (node (ref "H2") (pin "7") (pinfunction "7_7") (pintype "unspecified"))
      (node (ref "U1") (pin "67") (pinfunction "PC8_67") (pintype "unspecified"))
    )
    (net (code "57") (name "PC9") (class "Default")
      (node (ref "H2") (pin "8") (pinfunction "8_8") (pintype "unspecified"))
      (node (ref "U1") (pin "68") (pinfunction "PC9_68") (pintype "unspecified"))
    )
    (net (code "58") (name "PC10") (class "Default")
      (node (ref "H2") (pin "13") (pinfunction "13_13") (pintype "unspecified"))
      (node (ref "U1") (pin "79") (pinfunction "PC10_79") (pintype "unspecified"))
    )
    (net (code "59") (name "PC11") (class "Default")
      (node (ref "H2") (pin "14") (pinfunction "14_14") (pintype "unspecified"))
      (node (ref "U1") (pin "80") (pinfunction "PC11_80") (pintype "unspecified"))
    )
    (net (code "60") (name "PC12") (class "Default")
      (node (ref "H2") (pin "15") (pinfunction "15_15") (pintype "unspecified"))
      (node (ref "U1") (pin "81") (pinfunction "PC12_81") (pintype "unspecified"))
    )
    (net (code "61") (name "PD0") (class "Default")
      (node (ref "H2") (pin "16") (pinfunction "16_16") (pintype "unspecified"))
      (node (ref "U1") (pin "82") (pinfunction "PD0_82") (pintype "unspecified"))
    )
    (net (code "62") (name "PD1") (class "Default")
      (node (ref "H2") (pin "17") (pinfunction "17_17") (pintype "unspecified"))
      (node (ref "U1") (pin "83") (pinfunction "PD1_83") (pintype "unspecified"))
    )
    (net (code "63") (name "PD2") (class "Default")
      (node (ref "H2") (pin "18") (pinfunction "18_18") (pintype "unspecified"))
      (node (ref "U1") (pin "84") (pinfunction "PD2_84") (pintype "unspecified"))
    )
    (net (code "64") (name "PD3") (class "Default")
      (node (ref "H2") (pin "19") (pinfunction "19_19") (pintype "unspecified"))
      (node (ref "U1") (pin "85") (pinfunction "PD3_85") (pintype "unspecified"))
    )
    (net (code "65") (name "PD4") (class "Default")
      (node (ref "H2") (pin "20") (pinfunction "20_20") (pintype "unspecified"))
      (node (ref "U1") (pin "86") (pinfunction "PD4_86") (pintype "unspecified"))
    )
    (net (code "66") (name "PD5") (class "Default")
      (node (ref "H2") (pin "21") (pinfunction "21_21") (pintype "unspecified"))
      (node (ref "U1") (pin "87") (pinfunction "PD5_87") (pintype "unspecified"))
    )
    (net (code "67") (name "PD6") (class "Default")
      (node (ref "H2") (pin "22") (pinfunction "22_22") (pintype "unspecified"))
      (node (ref "U1") (pin "88") (pinfunction "PD6_88") (pintype "unspecified"))
    )
    (net (code "68") (name "PD7") (class "Default")
      (node (ref "H2") (pin "23") (pinfunction "23_23") (pintype "unspecified"))
      (node (ref "U1") (pin "89") (pinfunction "PD7_89") (pintype "unspecified"))
    )
    (net (code "69") (name "PD8") (class "Default")
      (node (ref "H1") (pin "9") (pinfunction "9_9") (pintype "unspecified"))
      (node (ref "U1") (pin "55") (pinfunction "PD8_55") (pintype "unspecified"))
    )
    (net (code "70") (name "PD9") (class "Default")
      (node (ref "H1") (pin "10") (pinfunction "10_10") (pintype "unspecified"))
      (node (ref "U1") (pin "56") (pinfunction "PD9_56") (pintype "unspecified"))
    )
    (net (code "71") (name "PD10") (class "Default")
      (node (ref "H1") (pin "7") (pinfunction "7_7") (pintype "unspecified"))
      (node (ref "U1") (pin "57") (pinfunction "PD10_57") (pintype "unspecified"))
    )
    (net (code "72") (name "PD11") (class "Default")
      (node (ref "H1") (pin "8") (pinfunction "8_8") (pintype "unspecified"))
      (node (ref "U1") (pin "58") (pinfunction "PD11_58") (pintype "unspecified"))
    )
    (net (code "73") (name "PD12") (class "Default")
      (node (ref "H1") (pin "5") (pinfunction "5_5") (pintype "unspecified"))
      (node (ref "U1") (pin "59") (pinfunction "PD12_59") (pintype "unspecified"))
    )
    (net (code "74") (name "PD13") (class "Default")
      (node (ref "H1") (pin "6") (pinfunction "6_6") (pintype "unspecified"))
      (node (ref "U1") (pin "60") (pinfunction "PD13_60") (pintype "unspecified"))
    )
    (net (code "75") (name "PD14") (class "Default")
      (node (ref "H1") (pin "3") (pinfunction "3_3") (pintype "unspecified"))
      (node (ref "U1") (pin "61") (pinfunction "PD14_61") (pintype "unspecified"))
    )
    (net (code "76") (name "PD15") (class "Default")
      (node (ref "H1") (pin "4") (pinfunction "4_4") (pintype "unspecified"))
      (node (ref "U1") (pin "62") (pinfunction "PD15_62") (pintype "unspecified"))
    )
    (net (code "77") (name "PE0") (class "Default")
      (node (ref "H2") (pin "30") (pinfunction "30_30") (pintype "unspecified"))
      (node (ref "U1") (pin "97") (pinfunction "PE0_97") (pintype "unspecified"))
    )
    (net (code "78") (name "PE1") (class "Default")
      (node (ref "H2") (pin "31") (pinfunction "31_31") (pintype "unspecified"))
      (node (ref "U1") (pin "98") (pinfunction "PE1_98") (pintype "unspecified"))
    )
    (net (code "79") (name "PE2") (class "Default")
      (node (ref "FPC1") (pin "6") (pinfunction "6_6") (pintype "unspecified"))
      (node (ref "H2") (pin "32") (pinfunction "32_32") (pintype "unspecified"))
      (node (ref "U1") (pin "1") (pinfunction "PE2_1") (pintype "unspecified"))
    )
    (net (code "80") (name "PE3") (class "Default")
      (node (ref "FPC1") (pin "8") (pinfunction "8_8") (pintype "unspecified"))
      (node (ref "H2") (pin "33") (pinfunction "33_33") (pintype "unspecified"))
      (node (ref "U1") (pin "2") (pinfunction "PE3_2") (pintype "unspecified"))
    )
    (net (code "81") (name "PE4") (class "Default")
      (node (ref "FPC1") (pin "3") (pinfunction "3_3") (pintype "unspecified"))
      (node (ref "H2") (pin "34") (pinfunction "34_34") (pintype "unspecified"))
      (node (ref "U1") (pin "3") (pinfunction "PE4_3") (pintype "unspecified"))
    )
    (net (code "82") (name "PE5") (class "Default")
      (node (ref "FPC1") (pin "4") (pinfunction "4_4") (pintype "unspecified"))
      (node (ref "H2") (pin "35") (pinfunction "35_35") (pintype "unspecified"))
      (node (ref "U1") (pin "4") (pinfunction "PE5_4") (pintype "unspecified"))
    )
    (net (code "83") (name "PE6") (class "Default")
      (node (ref "FPC1") (pin "5") (pinfunction "5_5") (pintype "unspecified"))
      (node (ref "H2") (pin "36") (pinfunction "36_36") (pintype "unspecified"))
      (node (ref "U1") (pin "5") (pinfunction "PE6_5") (pintype "unspecified"))
    )
    (net (code "84") (name "PE7") (class "Default")
      (node (ref "H1") (pin "26") (pinfunction "26_26") (pintype "unspecified"))
      (node (ref "U1") (pin "38") (pinfunction "PE7_38") (pintype "unspecified"))
    )
    (net (code "85") (name "PE8") (class "Default")
      (node (ref "H1") (pin "23") (pinfunction "23_23") (pintype "unspecified"))
      (node (ref "U1") (pin "39") (pinfunction "PE8_39") (pintype "unspecified"))
    )
    (net (code "86") (name "PE9") (class "Default")
      (node (ref "H1") (pin "24") (pinfunction "24_24") (pintype "unspecified"))
      (node (ref "U1") (pin "40") (pinfunction "PE9_40") (pintype "unspecified"))
    )
    (net (code "87") (name "PE10") (class "Default")
      (node (ref "H1") (pin "21") (pinfunction "21_21") (pintype "unspecified"))
      (node (ref "U1") (pin "41") (pinfunction "PE10_41") (pintype "unspecified"))
    )
    (net (code "88") (name "PE11") (class "Default")
      (node (ref "H1") (pin "22") (pinfunction "22_22") (pintype "unspecified"))
      (node (ref "U1") (pin "42") (pinfunction "PE11_42") (pintype "unspecified"))
    )
    (net (code "89") (name "PE12") (class "Default")
      (node (ref "H1") (pin "19") (pinfunction "19_19") (pintype "unspecified"))
      (node (ref "U1") (pin "43") (pinfunction "PE12_43") (pintype "unspecified"))
    )
    (net (code "90") (name "PE13") (class "Default")
      (node (ref "H1") (pin "20") (pinfunction "20_20") (pintype "unspecified"))
      (node (ref "U1") (pin "44") (pinfunction "PE13_44") (pintype "unspecified"))
    )
    (net (code "91") (name "PE14") (class "Default")
      (node (ref "H1") (pin "17") (pinfunction "17_17") (pintype "unspecified"))
      (node (ref "U1") (pin "45") (pinfunction "PE14_45") (pintype "unspecified"))
    )
    (net (code "92") (name "PE15") (class "Default")
      (node (ref "H1") (pin "18") (pinfunction "18_18") (pintype "unspecified"))
      (node (ref "U1") (pin "46") (pinfunction "PE15_46") (pintype "unspecified"))
    )
    (net (code "93") (name "PF2") (class "Default")
      (node (ref "H1") (pin "40") (pinfunction "40_40") (pintype "unspecified"))
      (node (ref "U1") (pin "19") (pinfunction "PF2_19") (pintype "unspecified"))
    )
    (net (code "94") (name "PF9") (class "Default")
      (node (ref "H2") (pin "37") (pinfunction "37_37") (pintype "unspecified"))
      (node (ref "U1") (pin "10") (pinfunction "PF9_10") (pintype "unspecified"))
    )
    (net (code "95") (name "PF10") (class "Default")
      (node (ref "H2") (pin "38") (pinfunction "38_38") (pintype "unspecified"))
      (node (ref "U1") (pin "11") (pinfunction "PF10_11") (pintype "unspecified"))
    )
    (net (code "96") (name "SWCLK") (class "Default")
      (node (ref "H3") (pin "1") (pinfunction "1_1") (pintype "unspecified"))
      (node (ref "U1") (pin "77") (pinfunction "PA14_77") (pintype "unspecified"))
    )
    (net (code "97") (name "SWDIO") (class "Default")
      (node (ref "H3") (pin "2") (pinfunction "2_2") (pintype "unspecified"))
      (node (ref "U1") (pin "76") (pinfunction "PA13_76") (pintype "unspecified"))
    )
    (net (code "98") (name "UART1_RX") (class "Default")
      (node (ref "U1") (pin "71") (pinfunction "PA10_71") (pintype "unspecified"))
      (node (ref "U5") (pin "6") (pinfunction "TXD_6") (pintype "unspecified"))
    )
    (net (code "99") (name "UART1_TX") (class "Default")
      (node (ref "U1") (pin "70") (pinfunction "PA9_70") (pintype "unspecified"))
      (node (ref "U5") (pin "7") (pinfunction "RXD_7") (pintype "unspecified"))
    )
    (net (code "100") (name "USB_DN") (class "Default")
      (node (ref "U5") (pin "2") (pinfunction "UD-_2") (pintype "unspecified"))
      (node (ref "USB1") (pin "A7") (pinfunction "DN1_A7") (pintype "unspecified"))
      (node (ref "USB1") (pin "B7") (pinfunction "DN2_B7") (pintype "unspecified"))
    )
    (net (code "101") (name "USB_DP") (class "Default")
      (node (ref "U5") (pin "1") (pinfunction "UD+_1") (pintype "unspecified"))
      (node (ref "USB1") (pin "A6") (pinfunction "DP1_A6") (pintype "unspecified"))
      (node (ref "USB1") (pin "B6") (pinfunction "DP2_B6") (pintype "unspecified"))
    )
    (net (code "102") (name "unconnected-(SW0-Pad1)") (class "Default")
      (node (ref "SW0") (pin "1") (pinfunction "1_1") (pintype "input+no_connect"))
    )
    (net (code "103") (name "unconnected-(SW1-Pad1)") (class "Default")
      (node (ref "SW1") (pin "1") (pinfunction "1_1") (pintype "input+no_connect"))
    )
    (net (code "104") (name "unconnected-(SW2-Pad1)") (class "Default")
      (node (ref "SW2") (pin "1") (pinfunction "1_1") (pintype "input+no_connect"))
    )
    (net (code "105") (name "unconnected-(SW3-Pad1)") (class "Default")
      (node (ref "SW3") (pin "1") (pinfunction "1_1") (pintype "input+no_connect"))
    )
    (net (code "106") (name "unconnected-(SW4-Pad1)") (class "Default")
      (node (ref "SW4") (pin "1") (pinfunction "1_1") (pintype "input+no_connect"))
    )
    (net (code "107") (name "unconnected-(U5-RTS#-Pad4)") (class "Default")
      (node (ref "U5") (pin "4") (pinfunction "RTS#_4") (pintype "unspecified+no_connect"))
    )
    (net (code "108") (name "unconnected-(USB1-CC1-PadA5)") (class "Default")
      (node (ref "USB1") (pin "A5") (pinfunction "CC1_A5") (pintype "unspecified+no_connect"))
    )
    (net (code "109") (name "unconnected-(USB1-CC2-PadB5)") (class "Default")
      (node (ref "USB1") (pin "B5") (pinfunction "CC2_B5") (pintype "unspecified+no_connect"))
    )
    (net (code "110") (name "unconnected-(USB1-SUB1-PadA8)") (class "Default")
      (node (ref "USB1") (pin "A8") (pinfunction "SUB1_A8") (pintype "unspecified+no_connect"))
    )
    (net (code "111") (name "unconnected-(USB1-SUB2-PadB8)") (class "Default")
      (node (ref "USB1") (pin "B8") (pinfunction "SUB2_B8") (pintype "unspecified+no_connect"))
    )
  )
)
